# Audio.net
KiCad netlist of a schematic drawn in Altium Designer
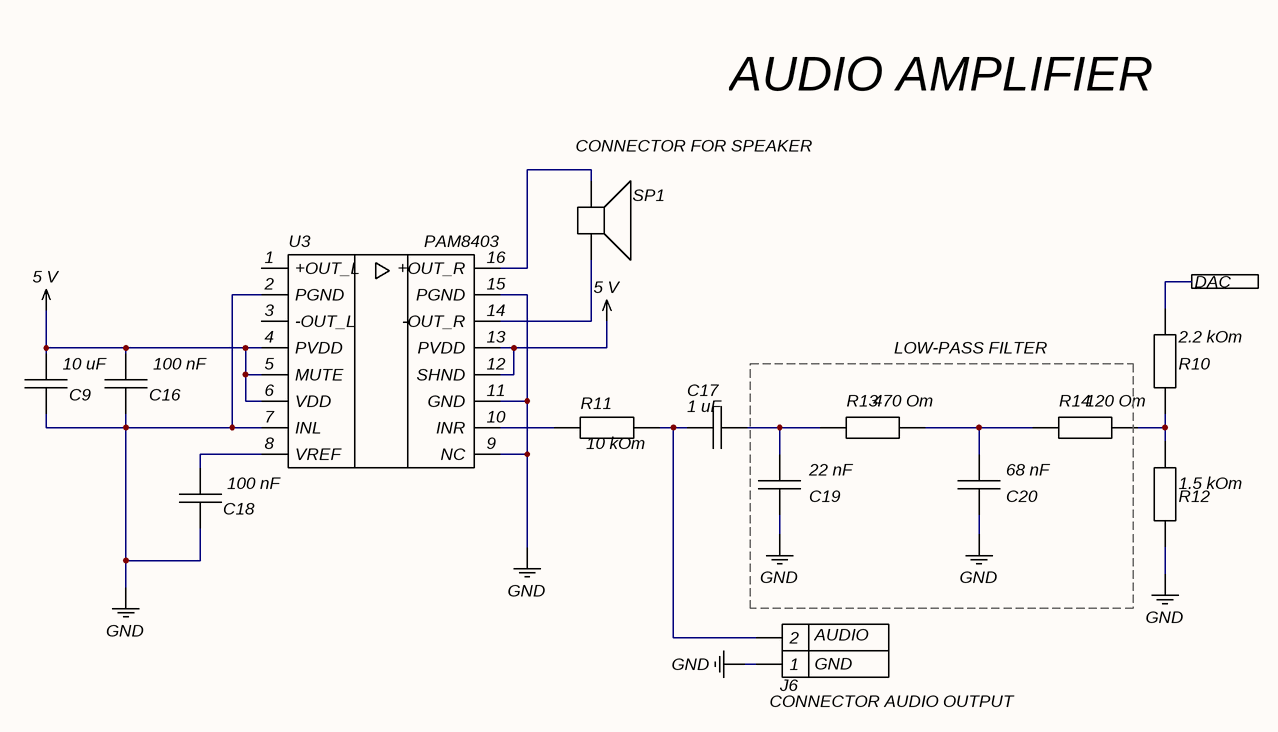
[diagram p0: Audio.SchDoc]

(export (version "E")
  (design (tool "Eeschema 10.0.6"))
  (components
    (comp (ref "C9") (value "10 uF") (footprint "0805") (libsource (lib "MyLib") (part "Cup")))
    (comp (ref "C16") (value "100 nF") (footprint "0805") (libsource (lib "MyLib") (part "Cup")))
    (comp (ref "C17") (value "1 uF") (footprint "0805") (libsource (lib "MyLib") (part "Cup")))
    (comp (ref "C18") (value "100 nF") (footprint "0805") (libsource (lib "MyLib") (part "Cup")))
    (comp (ref "C19") (value "22 nF") (footprint "0805") (libsource (lib "MyLib") (part "Cup")))
    (comp (ref "C20") (value "68 nF") (footprint "0805") (libsource (lib "MyLib") (part "Cup")))
    (comp (ref "J6") (value "2x2.54") (footprint "SMD 2x2.54") (libsource (lib "ECard_Lib") (part "2x2.54")))
    (comp (ref "R10") (value "2.2 kOm") (footprint "1206") (libsource (lib "MyLib") (part "Res")))
    (comp (ref "R11") (value "10 kOm") (footprint "0805") (libsource (lib "") (part "Res_1")))
    (comp (ref "R12") (value "1.5 kOm") (footprint "1206") (libsource (lib "MyLib") (part "Res")))
    (comp (ref "R13") (value "470 Om") (footprint "1206") (libsource (lib "") (part "Res_1")))
    (comp (ref "R14") (value "120 Om") (footprint "1206") (libsource (lib "") (part "Res_1")))
    (comp (ref "SP1") (value "speaker") (footprint "SMD 2x2.54") (libsource (lib "MyLib") (part "speaker")))
    (comp (ref "U3") (value "PAM8403") (footprint "sop16") (libsource (lib "ECard_Lib") (part "PAM8403")))
  )
  (nets
    (net (code "1") (name "/DAC") (class "Default")
      (node (ref "R10") (pin "2") (pinfunction "2_2") (pintype "passive"))
    )
    (net (code "2") (name "5 V") (class "Default")
      (node (ref "C16") (pin "2") (pinfunction "2_2") (pintype "passive"))
      (node (ref "C9") (pin "2") (pinfunction "2_2") (pintype "passive"))
      (node (ref "U3") (pin "12") (pinfunction "SHND_12") (pintype "passive"))
      (node (ref "U3") (pin "13") (pinfunction "PVDD_13") (pintype "passive"))
      (node (ref "U3") (pin "4") (pinfunction "PVDD_4") (pintype "passive"))
      (node (ref "U3") (pin "5") (pinfunction "MUTE_5") (pintype "passive"))
      (node (ref "U3") (pin "6") (pinfunction "VDD_6") (pintype "passive"))
    )
    (net (code "3") (name "GND") (class "Default")
      (node (ref "C16") (pin "1") (pinfunction "1_1") (pintype "passive"))
      (node (ref "C18") (pin "1") (pinfunction "1_1") (pintype "passive"))
      (node (ref "C19") (pin "1") (pinfunction "1_1") (pintype "passive"))
      (node (ref "C20") (pin "1") (pinfunction "1_1") (pintype "passive"))
      (node (ref "C9") (pin "1") (pinfunction "1_1") (pintype "passive"))
      (node (ref "J6") (pin "1") (pinfunction "1_1") (pintype "passive"))
      (node (ref "R12") (pin "1") (pinfunction "1_1") (pintype "passive"))
      (node (ref "U3") (pin "11") (pinfunction "GND_11") (pintype "passive"))
      (node (ref "U3") (pin "15") (pinfunction "PGND_15") (pintype "passive"))
      (node (ref "U3") (pin "2") (pinfunction "PGND_2") (pintype "passive"))
      (node (ref "U3") (pin "7") (pinfunction "INL_7") (pintype "passive"))
      (node (ref "U3") (pin "9") (pinfunction "NC_9") (pintype "passive"))
    )
    (net (code "4") (name "Net-(C17-Pad1)") (class "Default")
      (node (ref "C17") (pin "1") (pinfunction "1_1") (pintype "passive"))
      (node (ref "J6") (pin "2") (pinfunction "2_2") (pintype "passive"))
      (node (ref "R11") (pin "2") (pinfunction "2_2") (pintype "passive"))
    )
    (net (code "5") (name "Net-(C17-Pad2)") (class "Default")
      (node (ref "C17") (pin "2") (pinfunction "2_2") (pintype "passive"))
      (node (ref "C19") (pin "2") (pinfunction "2_2") (pintype "passive"))
      (node (ref "R13") (pin "1") (pinfunction "1_1") (pintype "passive"))
    )
    (net (code "6") (name "Net-(C20-Pad2)") (class "Default")
      (node (ref "C20") (pin "2") (pinfunction "2_2") (pintype "passive"))
      (node (ref "R13") (pin "2") (pinfunction "2_2") (pintype "passive"))
      (node (ref "R14") (pin "1") (pinfunction "1_1") (pintype "passive"))
    )
    (net (code "7") (name "Net-(R10-Pad1)") (class "Default")
      (node (ref "R10") (pin "1") (pinfunction "1_1") (pintype "passive"))
      (node (ref "R12") (pin "2") (pinfunction "2_2") (pintype "passive"))
      (node (ref "R14") (pin "2") (pinfunction "2_2") (pintype "passive"))
    )
    (net (code "8") (name "Net-(U3-+OUT_R)") (class "Default")
      (node (ref "SP1") (pin "2") (pinfunction "2_2") (pintype "passive"))
      (node (ref "U3") (pin "16") (pinfunction "+OUT_R_16") (pintype "passive"))
    )
    (net (code "9") (name "Net-(U3--OUT_R)") (class "Default")
      (node (ref "SP1") (pin "1") (pinfunction "1_1") (pintype "passive"))
      (node (ref "U3") (pin "14") (pinfunction "-OUT_R_14") (pintype "passive"))
    )
    (net (code "10") (name "Net-(U3-INR)") (class "Default")
      (node (ref "R11") (pin "1") (pinfunction "1_1") (pintype "passive"))
      (node (ref "U3") (pin "10") (pinfunction "INR_10") (pintype "passive"))
    )
    (net (code "11") (name "Net-(U3-VREF)") (class "Default")
      (node (ref "C18") (pin "2") (pinfunction "2_2") (pintype "passive"))
      (node (ref "U3") (pin "8") (pinfunction "VREF_8") (pintype "passive"))
    )
    (net (code "12") (name "unconnected-(U3-+OUT_L-Pad1)") (class "Default")
      (node (ref "U3") (pin "1") (pinfunction "+OUT_L_1") (pintype "passive"))
    )
    (net (code "13") (name "unconnected-(U3--OUT_L-Pad3)") (class "Default")
      (node (ref "U3") (pin "3") (pinfunction "-OUT_L_3") (pintype "passive"))
    )
  )
)
